# Arduino-Fio.net
KiCad netlist of a schematic drawn in EAGLE
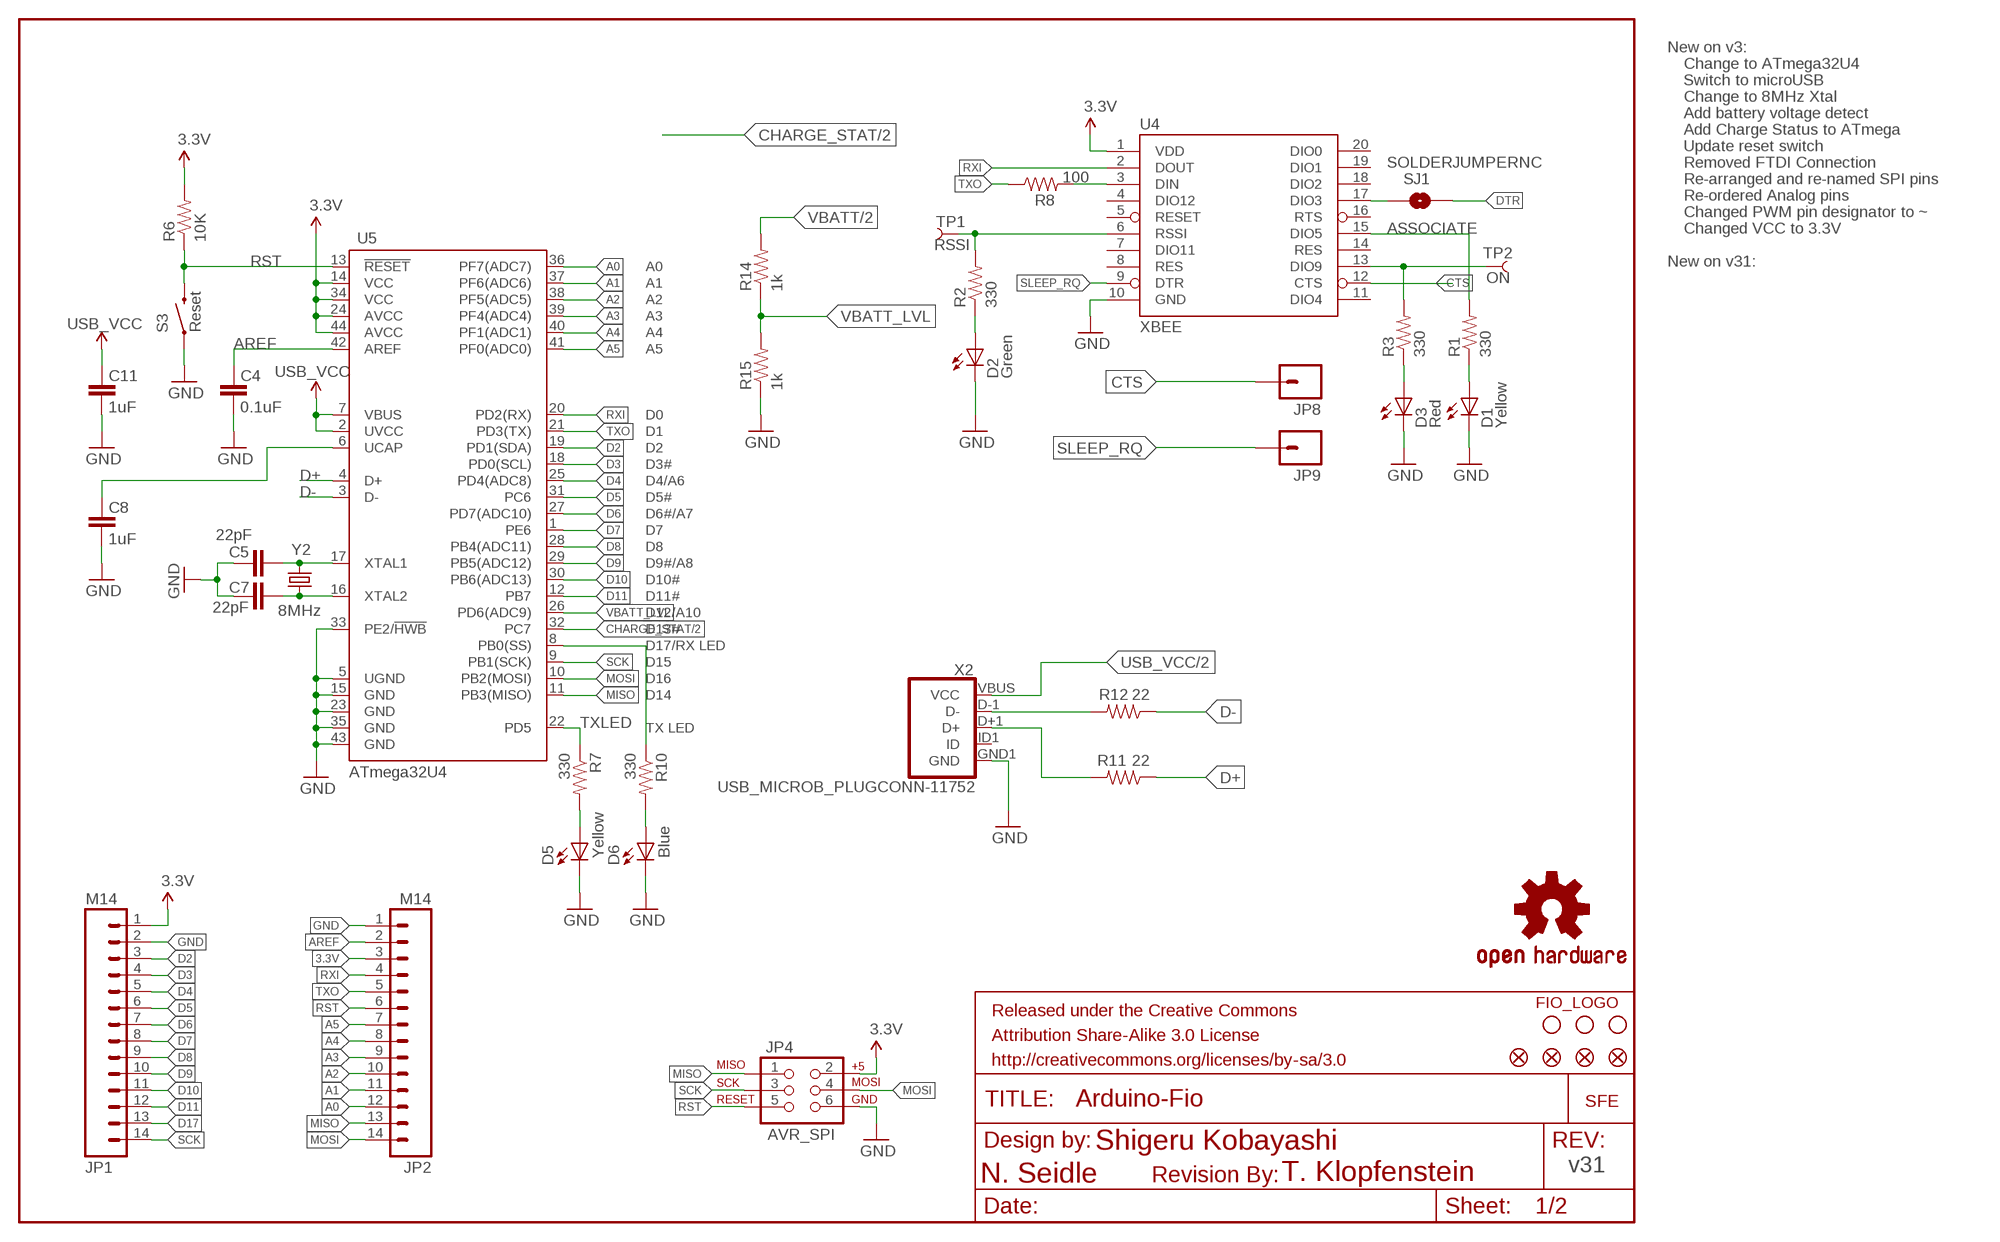
[diagram p0: schematic, sheet 1]
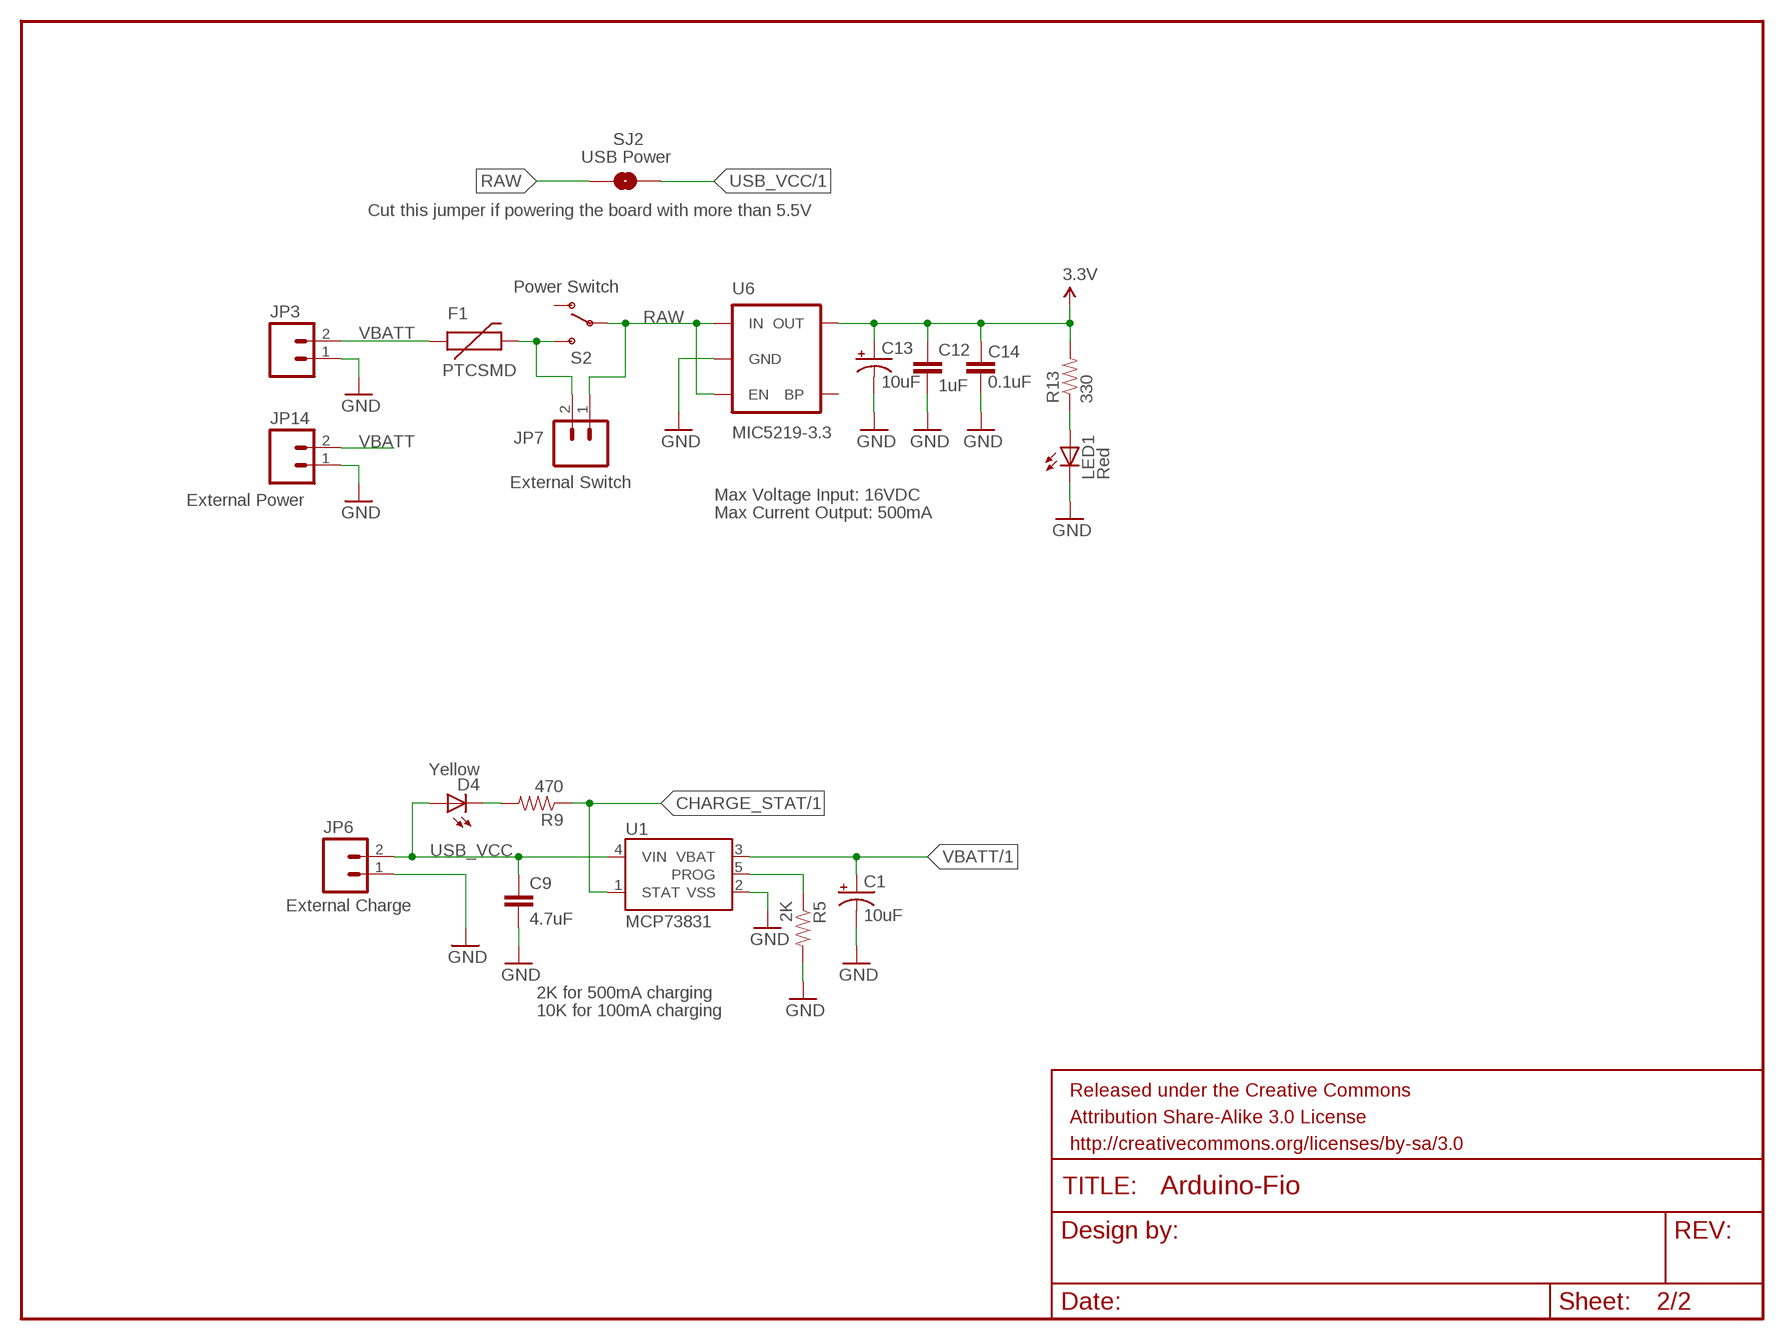
[diagram p1: schematic, sheet 2]

(export (version "E")
  (design (tool "Eeschema 10.0.6"))
  (components
    (comp (ref "C4")
      (value "0.1uF")
      (footprint "eagle-import:0603-CAP")
      (libsource (lib "eagle-import") (part "CAP0603-CAP"))
    )
    (comp (ref "C5")
      (value "22pF")
      (footprint "eagle-import:0603-CAP")
      (libsource (lib "eagle-import") (part "CAP0603-CAP"))
    )
    (comp (ref "C7")
      (value "22pF")
      (footprint "eagle-import:0603-CAP")
      (libsource (lib "eagle-import") (part "CAP0603-CAP"))
    )
    (comp (ref "C8")
      (value "1uF")
      (footprint "eagle-import:0603-CAP")
      (libsource (lib "eagle-import") (part "CAP0603-CAP"))
    )
    (comp (ref "C11")
      (value "1uF")
      (footprint "eagle-import:0603-CAP")
      (libsource (lib "eagle-import") (part "CAP0603-CAP"))
    )
    (comp (ref "D1")
      (value "Yellow")
      (footprint "eagle-import:LED-0603")
      (libsource (lib "eagle-import") (part "LED0603"))
    )
    (comp (ref "D2")
      (value "Green")
      (footprint "eagle-import:LED-0603")
      (libsource (lib "eagle-import") (part "LED0603"))
    )
    (comp (ref "D3")
      (value "Red")
      (footprint "eagle-import:LED-0603")
      (libsource (lib "eagle-import") (part "LED0603"))
    )
    (comp (ref "D5")
      (value "Yellow")
      (footprint "eagle-import:LED-0603")
      (libsource (lib "eagle-import") (part "LED0603"))
    )
    (comp (ref "D6")
      (value "Blue")
      (footprint "eagle-import:LED-0603")
      (libsource (lib "eagle-import") (part "LED0603"))
    )
    (comp (ref "FRAME1")
      (value "FRAME-LETTER")
      (footprint "eagle-import:CREATIVE_COMMONS")
      (libsource (lib "eagle-import") (part "FRAME-LETTER"))
    )
    (comp (ref "JP1")
      (value "M14")
      (footprint "eagle-import:1X14")
      (libsource (lib "eagle-import") (part "M14"))
    )
    (comp (ref "JP2")
      (value "M14")
      (footprint "eagle-import:1X14")
      (libsource (lib "eagle-import") (part "M14"))
    )
    (comp (ref "JP4")
      (value "AVR_SPI")
      (footprint "eagle-import:2X3")
      (libsource (lib "eagle-import") (part "AVR_SPI_PRG_6PTH"))
    )
    (comp (ref "JP5")
      (value "STAND-OFF")
      (footprint "eagle-import:STAND-OFF")
      (libsource (lib "eagle-import") (part "STAND-OFF"))
    )
    (comp (ref "JP8")
      (value "M01PTH")
      (footprint "eagle-import:1X01")
      (libsource (lib "eagle-import") (part "M01PTH"))
    )
    (comp (ref "JP9")
      (value "M01PTH")
      (footprint "eagle-import:1X01")
      (libsource (lib "eagle-import") (part "M01PTH"))
    )
    (comp (ref "JP10")
      (value "FIDUCIALUFIDUCIAL")
      (footprint "eagle-import:FIDUCIAL-1X2")
      (libsource (lib "eagle-import") (part "FIDUCIAL1X2"))
    )
    (comp (ref "JP11")
      (value "FIDUCIALUFIDUCIAL")
      (footprint "eagle-import:FIDUCIAL-1X2")
      (libsource (lib "eagle-import") (part "FIDUCIAL1X2"))
    )
    (comp (ref "JP12")
      (value "FIDUCIALUFIDUCIAL")
      (footprint "eagle-import:FIDUCIAL-1X2")
      (libsource (lib "eagle-import") (part "FIDUCIAL1X2"))
    )
    (comp (ref "JP13")
      (value "FIDUCIALUFIDUCIAL")
      (footprint "eagle-import:FIDUCIAL-1X2")
      (libsource (lib "eagle-import") (part "FIDUCIAL1X2"))
    )
    (comp (ref "JP16")
      (value "STAND-OFF")
      (footprint "eagle-import:STAND-OFF")
      (libsource (lib "eagle-import") (part "STAND-OFF"))
    )
    (comp (ref "JP17")
      (value "STAND-OFF")
      (footprint "eagle-import:STAND-OFF")
      (libsource (lib "eagle-import") (part "STAND-OFF"))
    )
    (comp (ref "LOGO1")
      (value "OSHW-LOGOL")
      (footprint "eagle-import:OSHW-LOGO-L")
      (libsource (lib "eagle-import") (part "OSHW-LOGOL"))
    )
    (comp (ref "R1")
      (value "330")
      (footprint "eagle-import:0603-RES")
      (libsource (lib "eagle-import") (part "RESISTOR0603-RES"))
    )
    (comp (ref "R2")
      (value "330")
      (footprint "eagle-import:0603-RES")
      (libsource (lib "eagle-import") (part "RESISTOR0603-RES"))
    )
    (comp (ref "R3")
      (value "330")
      (footprint "eagle-import:0603-RES")
      (libsource (lib "eagle-import") (part "RESISTOR0603-RES"))
    )
    (comp (ref "R6")
      (value "10K")
      (footprint "eagle-import:0603-RES")
      (libsource (lib "eagle-import") (part "RESISTOR0603-RES"))
    )
    (comp (ref "R7")
      (value "330")
      (footprint "eagle-import:0603-RES")
      (libsource (lib "eagle-import") (part "RESISTOR0603-RES"))
    )
    (comp (ref "R8")
      (value "100")
      (footprint "eagle-import:0603-RES")
      (libsource (lib "eagle-import") (part "RESISTOR0603-RES"))
    )
    (comp (ref "R10")
      (value "330")
      (footprint "eagle-import:0603-RES")
      (libsource (lib "eagle-import") (part "RESISTOR0603-RES"))
    )
    (comp (ref "R11")
      (value "22")
      (footprint "eagle-import:0603-RES")
      (libsource (lib "eagle-import") (part "RESISTOR0603-RES"))
    )
    (comp (ref "R12")
      (value "22")
      (footprint "eagle-import:0603-RES")
      (libsource (lib "eagle-import") (part "RESISTOR0603-RES"))
    )
    (comp (ref "R14")
      (value "1k")
      (footprint "eagle-import:0603-RES")
      (libsource (lib "eagle-import") (part "RESISTOR0603-RES"))
    )
    (comp (ref "R15")
      (value "1k")
      (footprint "eagle-import:0603-RES")
      (libsource (lib "eagle-import") (part "RESISTOR0603-RES"))
    )
    (comp (ref "S3")
      (value "Reset")
      (footprint "eagle-import:TACTILE_SWITCH_SMD")
      (libsource (lib "eagle-import") (part "SWITCH-MOMENTARY-2SMD"))
    )
    (comp (ref "SJ1")
      (value "SOLDERJUMPERNC")
      (footprint "eagle-import:SJ_2S")
      (libsource (lib "eagle-import") (part "SOLDERJUMPERNC"))
    )
    (comp (ref "TP1")
      (value "RSSI")
      (footprint "eagle-import:PAD.03X.05")
      (libsource (lib "eagle-import") (part "TEST-POINT3X5"))
    )
    (comp (ref "TP2")
      (value "ON")
      (footprint "eagle-import:PAD.03X.05")
      (libsource (lib "eagle-import") (part "TEST-POINT3X5"))
    )
    (comp (ref "U$1")
      (value "LOGO-SFENEW")
      (footprint "eagle-import:SFE-NEW-WEBLOGO")
      (libsource (lib "eagle-import") (part "LOGO-SFENEW"))
    )
    (comp (ref "U$2")
      (value "REVISION")
      (footprint "eagle-import:REVISION")
      (libsource (lib "eagle-import") (part "REVISION"))
    )
    (comp (ref "U$6")
      (value "FIO_LOGOV2")
      (footprint "eagle-import:FUNNEL_LOGO_BOTTOM_V2")
      (libsource (lib "eagle-import") (part "FIO_LOGOV2"))
    )
    (comp (ref "U4")
      (value "XBEE")
      (footprint "eagle-import:XBEE-SMD")
      (libsource (lib "eagle-import") (part "XBEE-1B3"))
    )
    (comp (ref "U5")
      (value "ATmega32U4")
      (footprint "eagle-import:QFN-44-NOPAD_1_1")
      (libsource (lib "eagle-import") (part "ATMEGA32U41{colon}1"))
    )
    (comp (ref "X2")
      (value "USB_MICROB_PLUGCONN-11752")
      (footprint "eagle-import:USB-B-MICRO-SMD_V03")
      (libsource (lib "eagle-import") (part "USB_MICROB_PLUGCONN-11752"))
    )
    (comp (ref "Y2")
      (value "8MHz")
      (footprint "eagle-import:CRYSTAL-SMD-5X3")
      (libsource (lib "eagle-import") (part "CRYSTAL5X3"))
    )
    (comp (ref "C1")
      (value "10uF")
      (footprint "eagle-import:EIA3216")
      (libsource (lib "eagle-import") (part "CAP_POL1206"))
    )
    (comp (ref "C9")
      (value "4.7uF")
      (footprint "eagle-import:0603-CAP")
      (libsource (lib "eagle-import") (part "CAP0603-CAP"))
    )
    (comp (ref "C12")
      (value "1uF")
      (footprint "eagle-import:0603-CAP")
      (libsource (lib "eagle-import") (part "CAP0603-CAP"))
    )
    (comp (ref "C13")
      (value "10uF")
      (footprint "eagle-import:EIA3216")
      (libsource (lib "eagle-import") (part "CAP_POL1206"))
    )
    (comp (ref "C14")
      (value "0.1uF")
      (footprint "eagle-import:0603-CAP")
      (libsource (lib "eagle-import") (part "CAP0603-CAP"))
    )
    (comp (ref "D4")
      (value "Yellow")
      (footprint "eagle-import:LED-0603")
      (libsource (lib "eagle-import") (part "LED0603"))
    )
    (comp (ref "F1")
      (value "PTCSMD")
      (footprint "eagle-import:PTC-1206")
      (libsource (lib "eagle-import") (part "PTCSMD"))
    )
    (comp (ref "FRAME2")
      (value "FRAME-LETTER")
      (footprint "eagle-import:CREATIVE_COMMONS")
      (libsource (lib "eagle-import") (part "FRAME-LETTER"))
    )
    (comp (ref "JP3")
      (value "M02-JST-2MM-SMT")
      (footprint "eagle-import:JST-2-SMD")
      (libsource (lib "eagle-import") (part "M02-JST-2MM-SMT"))
    )
    (comp (ref "JP6")
      (value "External Charge")
      (footprint "eagle-import:1X02")
      (libsource (lib "eagle-import") (part "M02PTH"))
    )
    (comp (ref "JP7")
      (value "External Switch")
      (footprint "eagle-import:1X02")
      (libsource (lib "eagle-import") (part "M02PTH"))
    )
    (comp (ref "JP14")
      (value "External Power")
      (footprint "eagle-import:1X02")
      (libsource (lib "eagle-import") (part "M02PTH"))
    )
    (comp (ref "LED1")
      (value "Red")
      (footprint "eagle-import:LED-0603")
      (libsource (lib "eagle-import") (part "LED0603"))
    )
    (comp (ref "R5")
      (value "2K")
      (footprint "eagle-import:0603-RES")
      (libsource (lib "eagle-import") (part "RESISTOR0603-RES"))
    )
    (comp (ref "R9")
      (value "470")
      (footprint "eagle-import:0603-RES")
      (libsource (lib "eagle-import") (part "RESISTOR0603-RES"))
    )
    (comp (ref "R13")
      (value "330")
      (footprint "eagle-import:0603-RES")
      (libsource (lib "eagle-import") (part "RESISTOR0603-RES"))
    )
    (comp (ref "S2")
      (value "Power Switch")
      (footprint "eagle-import:AYZ0202")
      (libsource (lib "eagle-import") (part "SWITCH-SPSTSMD"))
    )
    (comp (ref "SJ2")
      (value "USB Power")
      (footprint "eagle-import:SJ_2S-TRACE")
      (libsource (lib "eagle-import") (part "SOLDERJUMPERTRACE"))
    )
    (comp (ref "U1")
      (value "MCP73831")
      (footprint "eagle-import:SOT23-5")
      (libsource (lib "eagle-import") (part "MCP73831"))
    )
    (comp (ref "U6")
      (value "MIC5219-3.3")
      (footprint "eagle-import:SOT23-5")
      (libsource (lib "eagle-import") (part "V_REG_LDOSMD"))
    )
  )
  (nets
    (net (code "1") (name "3.3V") (class "Default")
      (node (ref "C12") (pin "1") (pinfunction "1_1") (pintype "passive"))
      (node (ref "C13") (pin "A") (pinfunction "+_A") (pintype "passive"))
      (node (ref "C14") (pin "2") (pinfunction "2_2") (pintype "passive"))
      (node (ref "JP1") (pin "1") (pinfunction "1_1") (pintype "passive"))
      (node (ref "JP2") (pin "3") (pinfunction "3_3") (pintype "passive"))
      (node (ref "JP4") (pin "2") (pinfunction "2_2") (pintype "passive"))
      (node (ref "R13") (pin "2") (pinfunction "2_2") (pintype "passive"))
      (node (ref "R6") (pin "2") (pinfunction "2_2") (pintype "passive"))
      (node (ref "U4") (pin "1") (pinfunction "VDD_1") (pintype "power_in"))
      (node (ref "U5") (pin "14") (pinfunction "VCC_14") (pintype "bidirectional"))
      (node (ref "U5") (pin "24") (pinfunction "AVCC_24") (pintype "bidirectional"))
      (node (ref "U5") (pin "34") (pinfunction "VCC_34") (pintype "bidirectional"))
      (node (ref "U5") (pin "44") (pinfunction "AVCC_44") (pintype "bidirectional"))
      (node (ref "U6") (pin "5") (pinfunction "OUT_5") (pintype "passive"))
    )
    (net (code "2") (name "A0") (class "Default")
      (node (ref "JP2") (pin "12") (pinfunction "12_12") (pintype "passive"))
      (node (ref "U5") (pin "36") (pinfunction "PF7(ADC7)_36") (pintype "bidirectional"))
    )
    (net (code "3") (name "A1") (class "Default")
      (node (ref "JP2") (pin "11") (pinfunction "11_11") (pintype "passive"))
      (node (ref "U5") (pin "37") (pinfunction "PF6(ADC6)_37") (pintype "bidirectional"))
    )
    (net (code "4") (name "A2") (class "Default")
      (node (ref "JP2") (pin "10") (pinfunction "10_10") (pintype "passive"))
      (node (ref "U5") (pin "38") (pinfunction "PF5(ADC5)_38") (pintype "bidirectional"))
    )
    (net (code "5") (name "A3") (class "Default")
      (node (ref "JP2") (pin "9") (pinfunction "9_9") (pintype "passive"))
      (node (ref "U5") (pin "39") (pinfunction "PF4(ADC4)_39") (pintype "bidirectional"))
    )
    (net (code "6") (name "A4") (class "Default")
      (node (ref "JP2") (pin "8") (pinfunction "8_8") (pintype "passive"))
      (node (ref "U5") (pin "40") (pinfunction "PF1(ADC1)_40") (pintype "bidirectional"))
    )
    (net (code "7") (name "A5") (class "Default")
      (node (ref "JP2") (pin "7") (pinfunction "7_7") (pintype "passive"))
      (node (ref "U5") (pin "41") (pinfunction "PF0(ADC0)_41") (pintype "bidirectional"))
    )
    (net (code "8") (name "AREF") (class "Default")
      (node (ref "C4") (pin "2") (pinfunction "2_2") (pintype "passive"))
      (node (ref "JP2") (pin "2") (pinfunction "2_2") (pintype "passive"))
      (node (ref "U5") (pin "42") (pinfunction "AREF_42") (pintype "bidirectional"))
    )
    (net (code "9") (name "ASSOCIATE") (class "Default")
      (node (ref "R1") (pin "2") (pinfunction "2_2") (pintype "passive"))
      (node (ref "U4") (pin "15") (pinfunction "DIO5_15") (pintype "bidirectional"))
    )
    (net (code "10") (name "CHARGE_STAT") (class "Default")
      (node (ref "R9") (pin "1") (pinfunction "1_1") (pintype "passive"))
      (node (ref "U1") (pin "1") (pinfunction "STAT_1") (pintype "output"))
      (node (ref "U5") (pin "32") (pinfunction "PC7_32") (pintype "bidirectional"))
    )
    (net (code "11") (name "CTS") (class "Default")
      (node (ref "JP8") (pin "1") (pinfunction "1_1") (pintype "passive"))
      (node (ref "U4") (pin "12") (pinfunction "CTS_12") (pintype "output"))
    )
    (net (code "12") (name "D+") (class "Default")
      (node (ref "R11") (pin "1") (pinfunction "1_1") (pintype "passive"))
      (node (ref "U5") (pin "4") (pinfunction "D+_4") (pintype "bidirectional"))
    )
    (net (code "13") (name "D-") (class "Default")
      (node (ref "R12") (pin "1") (pinfunction "1_1") (pintype "passive"))
      (node (ref "U5") (pin "3") (pinfunction "D-_3") (pintype "bidirectional"))
    )
    (net (code "14") (name "D2") (class "Default")
      (node (ref "JP1") (pin "3") (pinfunction "3_3") (pintype "passive"))
      (node (ref "U5") (pin "19") (pinfunction "PD1(SDA)_19") (pintype "bidirectional"))
    )
    (net (code "15") (name "D3") (class "Default")
      (node (ref "JP1") (pin "4") (pinfunction "4_4") (pintype "passive"))
      (node (ref "U5") (pin "18") (pinfunction "PD0(SCL)_18") (pintype "bidirectional"))
    )
    (net (code "16") (name "D4") (class "Default")
      (node (ref "JP1") (pin "5") (pinfunction "5_5") (pintype "passive"))
      (node (ref "U5") (pin "25") (pinfunction "PD4(ADC8)_25") (pintype "bidirectional"))
    )
    (net (code "17") (name "D5") (class "Default")
      (node (ref "JP1") (pin "6") (pinfunction "6_6") (pintype "passive"))
      (node (ref "U5") (pin "31") (pinfunction "PC6_31") (pintype "bidirectional"))
    )
    (net (code "18") (name "D6") (class "Default")
      (node (ref "JP1") (pin "7") (pinfunction "7_7") (pintype "passive"))
      (node (ref "U5") (pin "27") (pinfunction "PD7(ADC10)_27") (pintype "bidirectional"))
    )
    (net (code "19") (name "D7") (class "Default")
      (node (ref "JP1") (pin "8") (pinfunction "8_8") (pintype "passive"))
      (node (ref "U5") (pin "1") (pinfunction "PE6_1") (pintype "bidirectional"))
    )
    (net (code "20") (name "D8") (class "Default")
      (node (ref "JP1") (pin "9") (pinfunction "9_9") (pintype "passive"))
      (node (ref "U5") (pin "28") (pinfunction "PB4(ADC11)_28") (pintype "bidirectional"))
    )
    (net (code "21") (name "D9") (class "Default")
      (node (ref "JP1") (pin "10") (pinfunction "10_10") (pintype "passive"))
      (node (ref "U5") (pin "29") (pinfunction "PB5(ADC12)_29") (pintype "bidirectional"))
    )
    (net (code "22") (name "D10") (class "Default")
      (node (ref "JP1") (pin "11") (pinfunction "11_11") (pintype "passive"))
      (node (ref "U5") (pin "30") (pinfunction "PB6(ADC13)_30") (pintype "bidirectional"))
    )
    (net (code "23") (name "D11") (class "Default")
      (node (ref "JP1") (pin "12") (pinfunction "12_12") (pintype "passive"))
      (node (ref "U5") (pin "12") (pinfunction "PB7_12") (pintype "bidirectional"))
    )
    (net (code "24") (name "D17") (class "Default")
      (node (ref "JP1") (pin "13") (pinfunction "13_13") (pintype "passive"))
      (node (ref "R10") (pin "1") (pinfunction "1_1") (pintype "passive"))
      (node (ref "U5") (pin "8") (pinfunction "PB0(SS)_8") (pintype "bidirectional"))
    )
    (net (code "25") (name "DTR") (class "Default")
      (node (ref "SJ1") (pin "2") (pinfunction "2_2") (pintype "passive"))
    )
    (net (code "26") (name "GND") (class "Default")
      (node (ref "C1") (pin "C") (pinfunction "-_C") (pintype "passive"))
      (node (ref "C11") (pin "1") (pinfunction "1_1") (pintype "passive"))
      (node (ref "C12") (pin "2") (pinfunction "2_2") (pintype "passive"))
      (node (ref "C13") (pin "C") (pinfunction "-_C") (pintype "passive"))
      (node (ref "C14") (pin "1") (pinfunction "1_1") (pintype "passive"))
      (node (ref "C4") (pin "1") (pinfunction "1_1") (pintype "passive"))
      (node (ref "C5") (pin "2") (pinfunction "2_2") (pintype "passive"))
      (node (ref "C7") (pin "2") (pinfunction "2_2") (pintype "passive"))
      (node (ref "C8") (pin "1") (pinfunction "1_1") (pintype "passive"))
      (node (ref "C9") (pin "2") (pinfunction "2_2") (pintype "passive"))
      (node (ref "D1") (pin "C") (pinfunction "C_C") (pintype "passive"))
      (node (ref "D2") (pin "C") (pinfunction "C_C") (pintype "passive"))
      (node (ref "D3") (pin "C") (pinfunction "C_C") (pintype "passive"))
      (node (ref "D5") (pin "C") (pinfunction "C_C") (pintype "passive"))
      (node (ref "D6") (pin "C") (pinfunction "C_C") (pintype "passive"))
      (node (ref "JP1") (pin "2") (pinfunction "2_2") (pintype "passive"))
      (node (ref "JP14") (pin "1") (pinfunction "1_1") (pintype "passive"))
      (node (ref "JP2") (pin "1") (pinfunction "1_1") (pintype "passive"))
      (node (ref "JP3") (pin "1") (pinfunction "1_1") (pintype "passive"))
      (node (ref "JP4") (pin "6") (pinfunction "6_6") (pintype "passive"))
      (node (ref "JP6") (pin "1") (pinfunction "1_1") (pintype "passive"))
      (node (ref "LED1") (pin "C") (pinfunction "C_C") (pintype "passive"))
      (node (ref "R15") (pin "1") (pinfunction "1_1") (pintype "passive"))
      (node (ref "R5") (pin "2") (pinfunction "2_2") (pintype "passive"))
      (node (ref "S3") (pin "1") (pinfunction "1_1") (pintype "passive"))
      (node (ref "U1") (pin "2") (pinfunction "VSS_2") (pintype "power_in"))
      (node (ref "U4") (pin "10") (pinfunction "GND_10") (pintype "power_in"))
      (node (ref "U5") (pin "15") (pinfunction "GND_15") (pintype "bidirectional"))
      (node (ref "U5") (pin "23") (pinfunction "GND_23") (pintype "bidirectional"))
      (node (ref "U5") (pin "33") (pinfunction "PE2/~{HWB}_33") (pintype "bidirectional"))
      (node (ref "U5") (pin "35") (pinfunction "GND_35") (pintype "bidirectional"))
      (node (ref "U5") (pin "43") (pinfunction "GND_43") (pintype "bidirectional"))
      (node (ref "U5") (pin "5") (pinfunction "UGND_5") (pintype "bidirectional"))
      (node (ref "U6") (pin "2") (pinfunction "GND_2") (pintype "input"))
      (node (ref "X2") (pin "GND1") (pinfunction "GND_GND1") (pintype "bidirectional"))
    )
    (net (code "27") (name "MISO") (class "Default")
      (node (ref "JP2") (pin "13") (pinfunction "13_13") (pintype "passive"))
      (node (ref "JP4") (pin "1") (pinfunction "1_1") (pintype "passive"))
      (node (ref "U5") (pin "11") (pinfunction "PB3(MISO)_11") (pintype "bidirectional"))
    )
    (net (code "28") (name "MOSI") (class "Default")
      (node (ref "JP2") (pin "14") (pinfunction "14_14") (pintype "passive"))
      (node (ref "JP4") (pin "4") (pinfunction "4_4") (pintype "passive"))
      (node (ref "U5") (pin "10") (pinfunction "PB2(MOSI)_10") (pintype "bidirectional"))
    )
    (net (code "29") (name "Net-(D1-PadA)") (class "Default")
      (node (ref "D1") (pin "A") (pinfunction "A_A") (pintype "passive"))
      (node (ref "R1") (pin "1") (pinfunction "1_1") (pintype "passive"))
    )
    (net (code "30") (name "Net-(D2-PadA)") (class "Default")
      (node (ref "D2") (pin "A") (pinfunction "A_A") (pintype "passive"))
      (node (ref "R2") (pin "1") (pinfunction "1_1") (pintype "passive"))
    )
    (net (code "31") (name "Net-(D3-PadA)") (class "Default")
      (node (ref "D3") (pin "A") (pinfunction "A_A") (pintype "passive"))
      (node (ref "R3") (pin "1") (pinfunction "1_1") (pintype "passive"))
    )
    (net (code "32") (name "Net-(D4-PadC)") (class "Default")
      (node (ref "D4") (pin "C") (pinfunction "C_C") (pintype "passive"))
      (node (ref "R9") (pin "2") (pinfunction "2_2") (pintype "passive"))
    )
    (net (code "33") (name "Net-(D5-PadA)") (class "Default")
      (node (ref "D5") (pin "A") (pinfunction "A_A") (pintype "passive"))
      (node (ref "R7") (pin "2") (pinfunction "2_2") (pintype "passive"))
    )
    (net (code "34") (name "Net-(D6-PadA)") (class "Default")
      (node (ref "D6") (pin "A") (pinfunction "A_A") (pintype "passive"))
      (node (ref "R10") (pin "2") (pinfunction "2_2") (pintype "passive"))
    )
    (net (code "35") (name "Net-(LED1-PadA)") (class "Default")
      (node (ref "LED1") (pin "A") (pinfunction "A_A") (pintype "passive"))
      (node (ref "R13") (pin "1") (pinfunction "1_1") (pintype "passive"))
    )
    (net (code "36") (name "Net-(S2-S)") (class "Default")
      (node (ref "F1") (pin "2") (pinfunction "2_2") (pintype "bidirectional"))
      (node (ref "JP7") (pin "2") (pinfunction "2_2") (pintype "passive"))
      (node (ref "S2") (pin "3") (pinfunction "S_3") (pintype "passive"))
    )
    (net (code "37") (name "Net-(TP1-1)") (class "Default")
      (node (ref "R2") (pin "2") (pinfunction "2_2") (pintype "passive"))
      (node (ref "TP1") (pin "P$1") (pinfunction "1_P$1") (pintype "bidirectional"))
      (node (ref "U4") (pin "6") (pinfunction "RSSI_6") (pintype "bidirectional"))
    )
    (net (code "38") (name "Net-(TP2-1)") (class "Default")
      (node (ref "R3") (pin "2") (pinfunction "2_2") (pintype "passive"))
      (node (ref "TP2") (pin "P$1") (pinfunction "1_P$1") (pintype "bidirectional"))
      (node (ref "U4") (pin "13") (pinfunction "DIO9_13") (pintype "bidirectional"))
    )
    (net (code "39") (name "Net-(U1-PROG)") (class "Default")
      (node (ref "R5") (pin "1") (pinfunction "1_1") (pintype "passive"))
      (node (ref "U1") (pin "5") (pinfunction "PROG_5") (pintype "input"))
    )
    (net (code "40") (name "Net-(U4-DIN)") (class "Default")
      (node (ref "R8") (pin "2") (pinfunction "2_2") (pintype "passive"))
      (node (ref "U4") (pin "3") (pinfunction "DIN_3") (pintype "input"))
    )
    (net (code "41") (name "Net-(U4-DIO3)") (class "Default")
      (node (ref "SJ1") (pin "1") (pinfunction "1_1") (pintype "passive"))
      (node (ref "U4") (pin "17") (pinfunction "DIO3_17") (pintype "bidirectional"))
    )
    (net (code "42") (name "Net-(U5-UCAP)") (class "Default")
      (node (ref "C8") (pin "2") (pinfunction "2_2") (pintype "passive"))
      (node (ref "U5") (pin "6") (pinfunction "UCAP_6") (pintype "bidirectional"))
    )
    (net (code "43") (name "Net-(U5-XTAL1)") (class "Default")
      (node (ref "C5") (pin "1") (pinfunction "1_1") (pintype "passive"))
      (node (ref "U5") (pin "17") (pinfunction "XTAL1_17") (pintype "bidirectional"))
      (node (ref "Y2") (pin "3") (pinfunction "2_3") (pintype "passive"))
    )
    (net (code "44") (name "Net-(U5-XTAL2)") (class "Default")
      (node (ref "C7") (pin "1") (pinfunction "1_1") (pintype "passive"))
      (node (ref "U5") (pin "16") (pinfunction "XTAL2_16") (pintype "bidirectional"))
      (node (ref "Y2") (pin "1") (pinfunction "1_1") (pintype "passive"))
    )
    (net (code "45") (name "Net-(X2-D+)") (class "Default")
      (node (ref "R11") (pin "2") (pinfunction "2_2") (pintype "passive"))
      (node (ref "X2") (pin "D+1") (pinfunction "D+_D+1") (pintype "bidirectional"))
    )
    (net (code "46") (name "Net-(X2-D-)") (class "Default")
      (node (ref "R12") (pin "2") (pinfunction "2_2") (pintype "passive"))
      (node (ref "X2") (pin "D-1") (pinfunction "D-_D-1") (pintype "bidirectional"))
    )
    (net (code "47") (name "RAW") (class "Default")
      (node (ref "JP7") (pin "1") (pinfunction "1_1") (pintype "passive"))
      (node (ref "S2") (pin "2") (pinfunction "P_2") (pintype "passive"))
      (node (ref "SJ2") (pin "1") (pinfunction "1_1") (pintype "passive"))
      (node (ref "U6") (pin "1") (pinfunction "IN_1") (pintype "input"))
      (node (ref "U6") (pin "3") (pinfunction "EN_3") (pintype "input"))
    )
    (net (code "48") (name "RST") (class "Default")
      (node (ref "JP2") (pin "6") (pinfunction "6_6") (pintype "passive"))
      (node (ref "JP4") (pin "5") (pinfunction "5_5") (pintype "passive"))
      (node (ref "R6") (pin "1") (pinfunction "1_1") (pintype "passive"))
      (node (ref "S3") (pin "3") (pinfunction "2_3") (pintype "passive"))
      (node (ref "U5") (pin "13") (pinfunction "~{RESET}_13") (pintype "bidirectional"))
    )
    (net (code "49") (name "RXI") (class "Default")
      (node (ref "JP2") (pin "4") (pinfunction "4_4") (pintype "passive"))
      (node (ref "U4") (pin "2") (pinfunction "DOUT_2") (pintype "output"))
      (node (ref "U5") (pin "20") (pinfunction "PD2(RX)_20") (pintype "bidirectional"))
    )
    (net (code "50") (name "SCK") (class "Default")
      (node (ref "JP1") (pin "14") (pinfunction "14_14") (pintype "passive"))
      (node (ref "JP4") (pin "3") (pinfunction "3_3") (pintype "passive"))
      (node (ref "U5") (pin "9") (pinfunction "PB1(SCK)_9") (pintype "bidirectional"))
    )
    (net (code "51") (name "SLEEP_RQ") (class "Default")
      (node (ref "JP9") (pin "1") (pinfunction "1_1") (pintype "passive"))
      (node (ref "U4") (pin "9") (pinfunction "DTR_9") (pintype "bidirectional"))
    )
    (net (code "52") (name "TXLED") (class "Default")
      (node (ref "R7") (pin "1") (pinfunction "1_1") (pintype "passive"))
      (node (ref "U5") (pin "22") (pinfunction "PD5_22") (pintype "bidirectional"))
    )
    (net (code "53") (name "TXO") (class "Default")
      (node (ref "JP2") (pin "5") (pinfunction "5_5") (pintype "passive"))
      (node (ref "R8") (pin "1") (pinfunction "1_1") (pintype "passive"))
      (node (ref "U5") (pin "21") (pinfunction "PD3(TX)_21") (pintype "bidirectional"))
    )
    (net (code "54") (name "USB_VCC") (class "Default")
      (node (ref "C11") (pin "2") (pinfunction "2_2") (pintype "passive"))
      (node (ref "C9") (pin "1") (pinfunction "1_1") (pintype "passive"))
      (node (ref "D4") (pin "A") (pinfunction "A_A") (pintype "passive"))
      (node (ref "JP6") (pin "2") (pinfunction "2_2") (pintype "passive"))
      (node (ref "SJ2") (pin "2") (pinfunction "2_2") (pintype "passive"))
      (node (ref "U1") (pin "4") (pinfunction "VIN_4") (pintype "power_in"))
      (node (ref "U5") (pin "2") (pinfunction "UVCC_2") (pintype "bidirectional"))
      (node (ref "U5") (pin "7") (pinfunction "VBUS_7") (pintype "bidirectional"))
      (node (ref "X2") (pin "VBUS") (pinfunction "VCC_VBUS") (pintype "bidirectional"))
    )
    (net (code "55") (name "VBATT") (class "Default")
      (node (ref "C1") (pin "A") (pinfunction "+_A") (pintype "passive"))
      (node (ref "F1") (pin "1") (pinfunction "1_1") (pintype "bidirectional"))
      (node (ref "JP14") (pin "2") (pinfunction "2_2") (pintype "passive"))
      (node (ref "JP3") (pin "2") (pinfunction "2_2") (pintype "passive"))
      (node (ref "R14") (pin "2") (pinfunction "2_2") (pintype "passive"))
      (node (ref "U1") (pin "3") (pinfunction "VBAT_3") (pintype "power_in"))
    )
    (net (code "56") (name "VBATT_LVL") (class "Default")
      (node (ref "R14") (pin "1") (pinfunction "1_1") (pintype "passive"))
      (node (ref "R15") (pin "2") (pinfunction "2_2") (pintype "passive"))
      (node (ref "U5") (pin "26") (pinfunction "PD6(ADC9)_26") (pintype "bidirectional"))
    )
    (net (code "57") (name "unconnected-(S2-O-Pad1)") (class "Default")
      (node (ref "S2") (pin "1") (pinfunction "O_1") (pintype "passive"))
    )
    (net (code "58") (name "unconnected-(U4-DIO0-Pad20)") (class "Default")
      (node (ref "U4") (pin "20") (pinfunction "DIO0_20") (pintype "bidirectional"))
    )
    (net (code "59") (name "unconnected-(U4-DIO1-Pad19)") (class "Default")
      (node (ref "U4") (pin "19") (pinfunction "DIO1_19") (pintype "bidirectional"))
    )
    (net (code "60") (name "unconnected-(U4-DIO2-Pad18)") (class "Default")
      (node (ref "U4") (pin "18") (pinfunction "DIO2_18") (pintype "bidirectional"))
    )
    (net (code "61") (name "unconnected-(U4-DIO4-Pad11)") (class "Default")
      (node (ref "U4") (pin "11") (pinfunction "DIO4_11") (pintype "bidirectional"))
    )
    (net (code "62") (name "unconnected-(U4-DIO11-Pad7)") (class "Default")
      (node (ref "U4") (pin "7") (pinfunction "DIO11_7") (pintype "bidirectional"))
    )
    (net (code "63") (name "unconnected-(U4-DIO12-Pad4)") (class "Default")
      (node (ref "U4") (pin "4") (pinfunction "DIO12_4") (pintype "bidirectional"))
    )
    (net (code "64") (name "unconnected-(U4-RES-Pad8)") (class "Default")
      (node (ref "U4") (pin "8") (pinfunction "RES_8") (pintype "bidirectional"))
    )
    (net (code "65") (name "unconnected-(U4-RES-Pad14)") (class "Default")
      (node (ref "U4") (pin "14") (pinfunction "RES_14") (pintype "bidirectional"))
    )
    (net (code "66") (name "unconnected-(U4-RESET-Pad5)") (class "Default")
      (node (ref "U4") (pin "5") (pinfunction "RESET_5") (pintype "input"))
    )
    (net (code "67") (name "unconnected-(U4-RTS-Pad16)") (class "Default")
      (node (ref "U4") (pin "16") (pinfunction "RTS_16") (pintype "input"))
    )
    (net (code "68") (name "unconnected-(U6-BP-Pad4)") (class "Default")
      (node (ref "U6") (pin "4") (pinfunction "BP_4") (pintype "input"))
    )
    (net (code "69") (name "unconnected-(X2-ID-PadID1)") (class "Default")
      (node (ref "X2") (pin "ID1") (pinfunction "ID_ID1") (pintype "bidirectional"))
    )
  )
)
